# Sheet2.net
KiCad netlist of a schematic drawn in Altium Designer
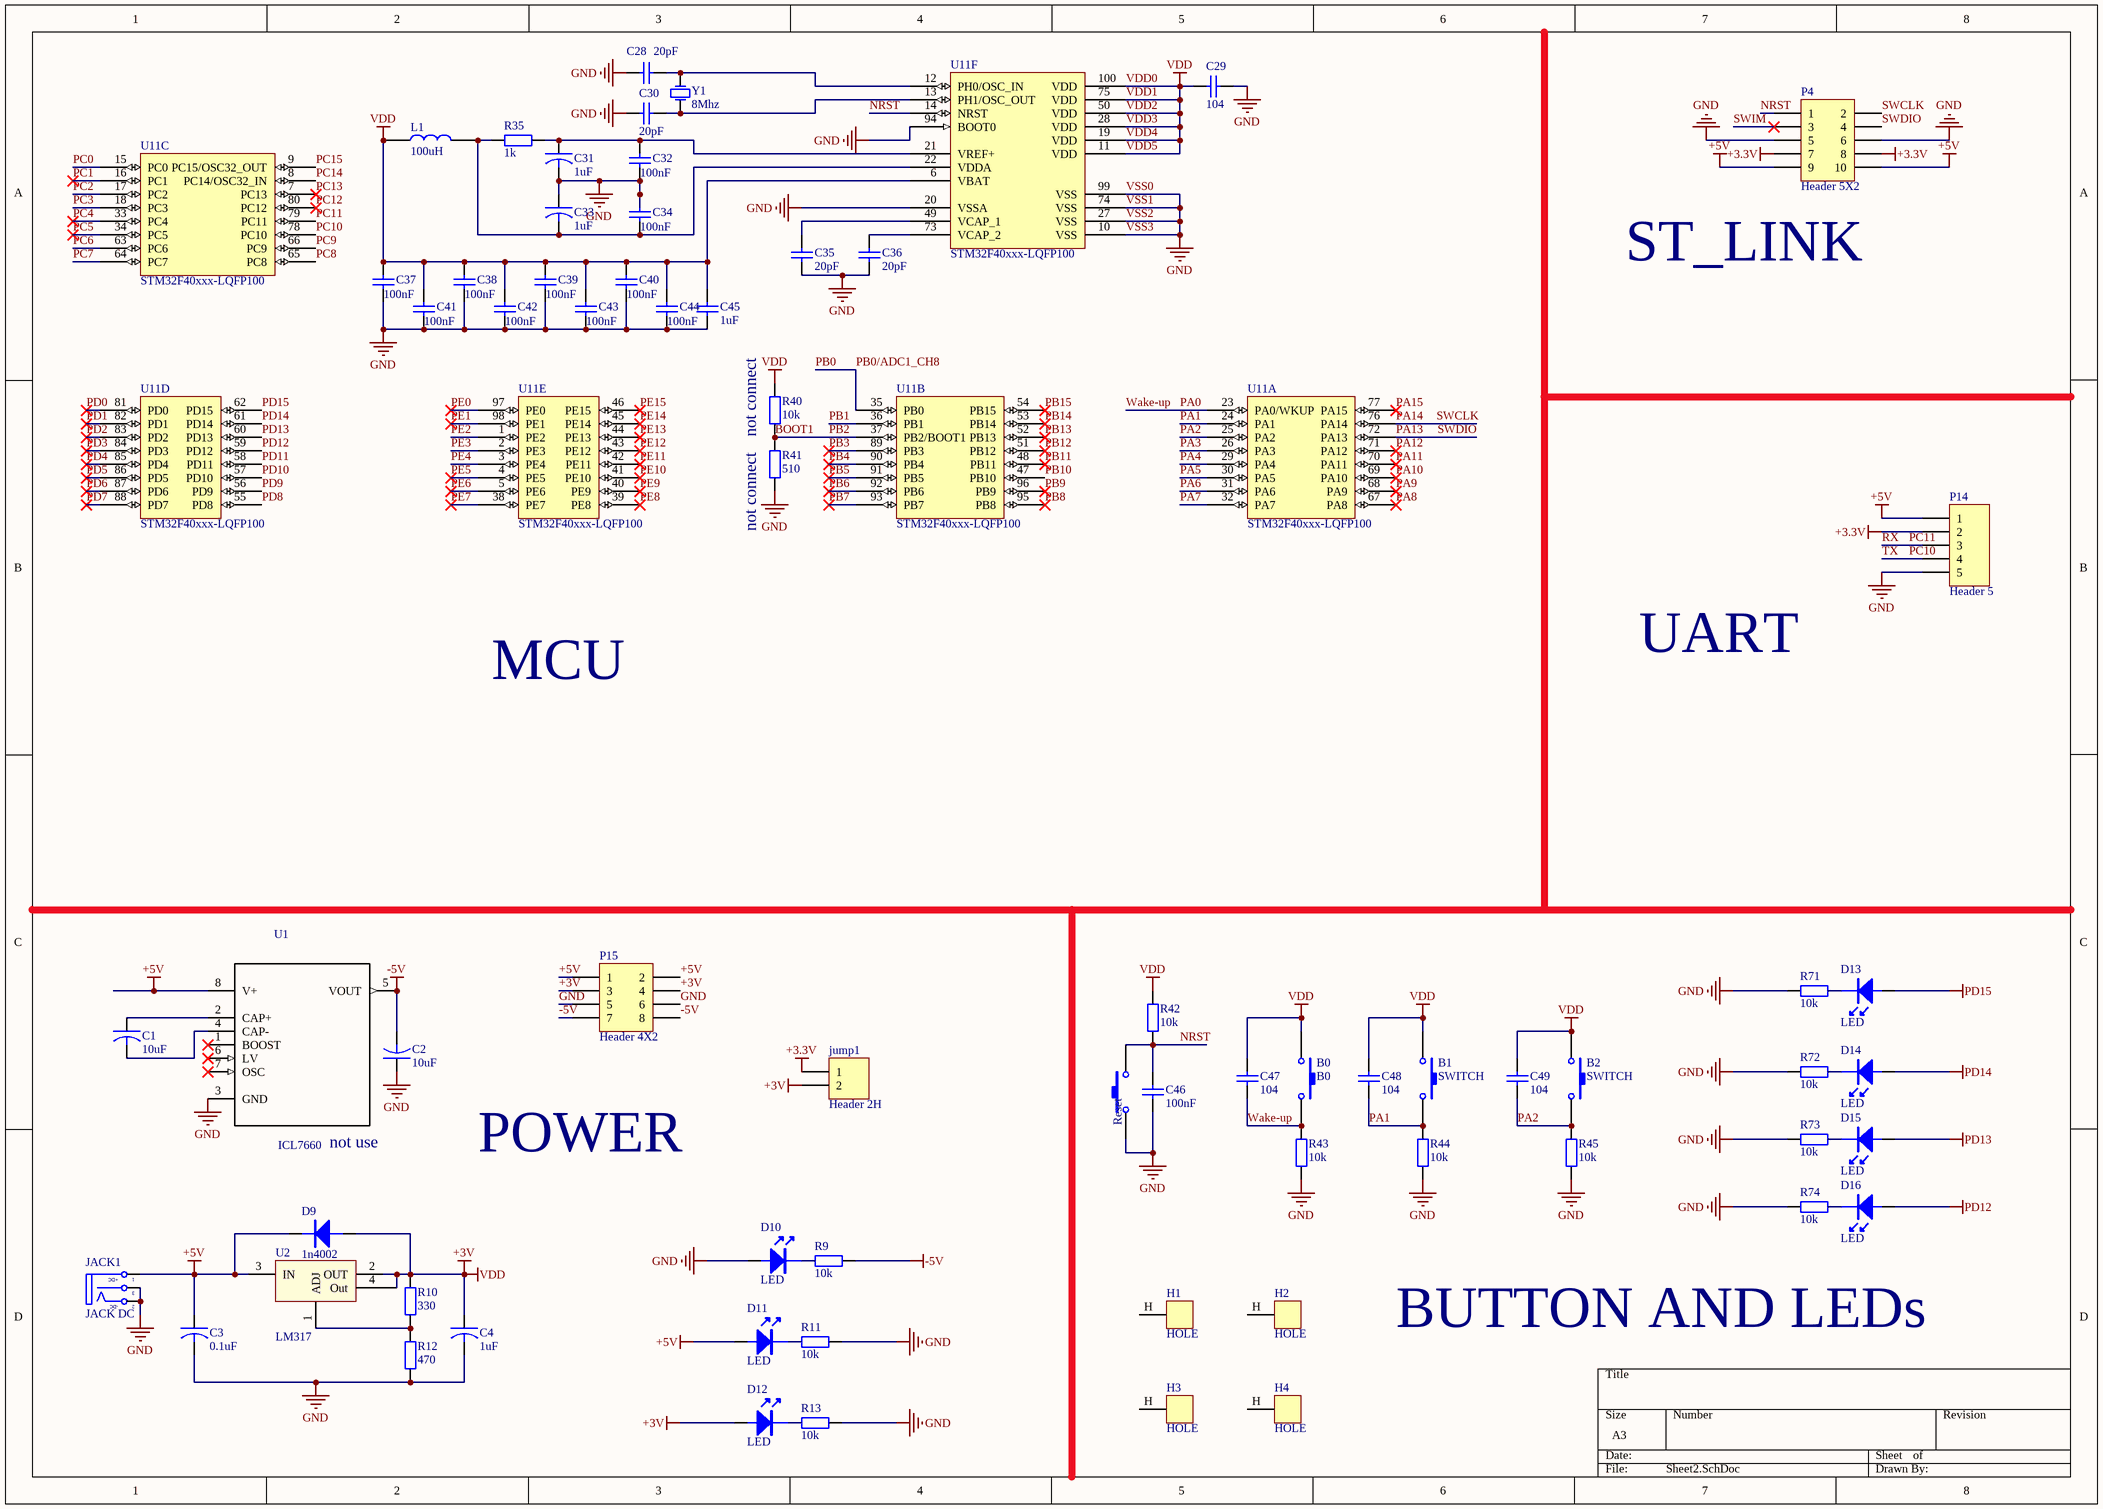
[diagram p0: Sheet2.SchDoc]

(export (version "E")
  (design (tool "Eeschema 10.0.6"))
  (components
    (comp (ref "B0")
      (value "B0")
      (footprint "SW 4PIN")
      (fields (field (name "PUBLISHER") "Altium Limited"))
      (libsource (lib "ThinhNguyenLib") (part "SWITCH"))
    )
    (comp (ref "B1")
      (value "SWITCH")
      (footprint "SW 4PIN")
      (fields (field (name "PUBLISHER") "Altium Limited"))
      (libsource (lib "ThinhNguyenLib") (part "SWITCH"))
    )
    (comp (ref "B2")
      (value "SWITCH")
      (footprint "SW 4PIN")
      (fields (field (name "PUBLISHER") "Altium Limited"))
      (libsource (lib "ThinhNguyenLib") (part "SWITCH"))
    )
    (comp (ref "C1")
      (value "10uF")
      (footprint "Miscellaneous Devices:3.5X2.8X1.9")
      (libsource (lib "ThinhNguyenLib") (part "CAPACITOR"))
    )
    (comp (ref "C2")
      (value "10uF")
      (footprint "Miscellaneous Devices:3.5X2.8X1.9")
      (libsource (lib "ThinhNguyenLib") (part "CAPACITOR"))
    )
    (comp (ref "C3")
      (value "0.1uF")
      (footprint "Miscellaneous Devices:3.5X2.8X1.9")
      (libsource (lib "ThinhNguyenLib") (part "CAPACITOR"))
    )
    (comp (ref "C4")
      (value "1uF")
      (footprint "Miscellaneous Devices:3.5X2.8X1.9")
      (libsource (lib "ThinhNguyenLib") (part "CAPACITOR"))
    )
    (comp (ref "C28")
      (value "20pF")
      (footprint "0805 CAP")
      (fields (field (name "PUBLISHER") "Altium Limited"))
      (libsource (lib "ThinhNguyenLib") (part "CAP CERAMIC"))
    )
    (comp (ref "C29")
      (value "104")
      (footprint "0805 CAP")
      (fields (field (name "PUBLISHER") "Altium Limited"))
      (libsource (lib "ThinhNguyenLib") (part "CAP CERAMIC"))
    )
    (comp (ref "C30")
      (value "20pF")
      (footprint "0805 CAP")
      (fields (field (name "PUBLISHER") "Altium Limited"))
      (libsource (lib "ThinhNguyenLib") (part "CAP CERAMIC"))
    )
    (comp (ref "C31")
      (value "1uF")
      (footprint "Miscellaneous Devices:3.5X2.8X1.9")
      (libsource (lib "ThinhNguyenLib") (part "CAPACITOR"))
    )
    (comp (ref "C32")
      (value "100nF")
      (footprint "0805 CAP")
      (fields (field (name "PUBLISHER") "Altium Limited"))
      (libsource (lib "ThinhNguyenLib") (part "CAP CERAMIC"))
    )
    (comp (ref "C33")
      (value "1uF")
      (footprint "Miscellaneous Devices:3.5X2.8X1.9")
      (libsource (lib "ThinhNguyenLib") (part "CAPACITOR"))
    )
    (comp (ref "C34")
      (value "100nF")
      (footprint "0805 CAP")
      (fields (field (name "PUBLISHER") "Altium Limited"))
      (libsource (lib "ThinhNguyenLib") (part "CAP CERAMIC"))
    )
    (comp (ref "C35")
      (value "20pF")
      (footprint "0805 CAP")
      (fields (field (name "PUBLISHER") "Altium Limited"))
      (libsource (lib "ThinhNguyenLib") (part "CAP CERAMIC"))
    )
    (comp (ref "C36")
      (value "20pF")
      (footprint "0805 CAP")
      (fields (field (name "PUBLISHER") "Altium Limited"))
      (libsource (lib "ThinhNguyenLib") (part "CAP CERAMIC"))
    )
    (comp (ref "C37")
      (value "100nF")
      (footprint "0805 CAP")
      (fields (field (name "PUBLISHER") "Altium Limited"))
      (libsource (lib "ThinhNguyenLib") (part "CAP CERAMIC"))
    )
    (comp (ref "C38")
      (value "100nF")
      (footprint "0805 CAP")
      (fields (field (name "PUBLISHER") "Altium Limited"))
      (libsource (lib "ThinhNguyenLib") (part "CAP CERAMIC"))
    )
    (comp (ref "C39")
      (value "100nF")
      (footprint "0805 CAP")
      (fields (field (name "PUBLISHER") "Altium Limited"))
      (libsource (lib "ThinhNguyenLib") (part "CAP CERAMIC"))
    )
    (comp (ref "C40")
      (value "100nF")
      (footprint "0805 CAP")
      (fields (field (name "PUBLISHER") "Altium Limited"))
      (libsource (lib "ThinhNguyenLib") (part "CAP CERAMIC"))
    )
    (comp (ref "C41")
      (value "100nF")
      (footprint "0805 CAP")
      (fields (field (name "PUBLISHER") "Altium Limited"))
      (libsource (lib "ThinhNguyenLib") (part "CAP CERAMIC"))
    )
    (comp (ref "C42")
      (value "100nF")
      (footprint "0805 CAP")
      (fields (field (name "PUBLISHER") "Altium Limited"))
      (libsource (lib "ThinhNguyenLib") (part "CAP CERAMIC"))
    )
    (comp (ref "C43")
      (value "100nF")
      (footprint "0805 CAP")
      (fields (field (name "PUBLISHER") "Altium Limited"))
      (libsource (lib "ThinhNguyenLib") (part "CAP CERAMIC"))
    )
    (comp (ref "C44")
      (value "100nF")
      (footprint "0805 CAP")
      (fields (field (name "PUBLISHER") "Altium Limited"))
      (libsource (lib "ThinhNguyenLib") (part "CAP CERAMIC"))
    )
    (comp (ref "C45")
      (value "1uF")
      (footprint "0805 CAP")
      (fields (field (name "PUBLISHER") "Altium Limited"))
      (libsource (lib "ThinhNguyenLib") (part "CAP CERAMIC"))
    )
    (comp (ref "C46")
      (value "100nF")
      (footprint "0805 CAP")
      (fields (field (name "PUBLISHER") "Altium Limited"))
      (libsource (lib "THINHDUILIB") (part "CAP CERAMIC"))
    )
    (comp (ref "C47")
      (value "104")
      (footprint "0805 CAP")
      (fields (field (name "PUBLISHER") "Altium Limited"))
      (libsource (lib "ThinhNguyenLib") (part "CAP CERAMIC"))
    )
    (comp (ref "C48")
      (value "104")
      (footprint "0805 CAP")
      (fields (field (name "PUBLISHER") "Altium Limited"))
      (libsource (lib "ThinhNguyenLib") (part "CAP CERAMIC"))
    )
    (comp (ref "C49")
      (value "104")
      (footprint "0805 CAP")
      (fields (field (name "PUBLISHER") "Altium Limited"))
      (libsource (lib "ThinhNguyenLib") (part "CAP CERAMIC"))
    )
    (comp (ref "D9")
      (value "1n4002")
      (footprint "DIODE SMA")
      (libsource (lib "ThinhNguyenLib") (part "DIODE"))
    )
    (comp (ref "D10")
      (value "LED")
      (footprint "LED SMD 0805")
      (libsource (lib "ThinhNguyenLib") (part "LED"))
    )
    (comp (ref "D11")
      (value "LED")
      (footprint "LED SMD 0805")
      (libsource (lib "ThinhNguyenLib") (part "LED"))
    )
    (comp (ref "D12")
      (value "LED")
      (footprint "LED SMD 0805")
      (libsource (lib "ThinhNguyenLib") (part "LED"))
    )
    (comp (ref "D13")
      (value "LED")
      (footprint "LED SMD 0805")
      (libsource (lib "ThinhNguyenLib") (part "LED"))
    )
    (comp (ref "D14")
      (value "LED")
      (footprint "LED SMD 0805")
      (libsource (lib "ThinhNguyenLib") (part "LED"))
    )
    (comp (ref "D15")
      (value "LED")
      (footprint "LED SMD 0805")
      (libsource (lib "ThinhNguyenLib") (part "LED"))
    )
    (comp (ref "D16")
      (value "LED")
      (footprint "LED SMD 0805")
      (libsource (lib "ThinhNguyenLib") (part "LED"))
    )
    (comp (ref "H1") (value "HOLE") (footprint "HOLE") (libsource (lib "ThinhNguyenLib") (part "HOLE")))
    (comp (ref "H2") (value "HOLE") (footprint "HOLE") (libsource (lib "ThinhNguyenLib") (part "HOLE")))
    (comp (ref "H3") (value "HOLE") (footprint "HOLE") (libsource (lib "ThinhNguyenLib") (part "HOLE")))
    (comp (ref "H4") (value "HOLE") (footprint "HOLE") (libsource (lib "ThinhNguyenLib") (part "HOLE")))
    (comp (ref "JACK1")
      (value "JACK DC")
      (footprint "JACK DC")
      (libsource (lib "ThinhNguyenLib") (part "JACK DC"))
    )
    (comp (ref "jump1")
      (value "Header 2H")
      (footprint "HDR1X2")
      (fields (field (name "PUBLISHER") "Altium Limited"))
      (libsource (lib "ThinhNguyenLib") (part "Header 2H"))
    )
    (comp (ref "L1")
      (value "100uH")
      (footprint "1206 Negro")
      (libsource (lib "ThinhNguyenLib") (part "INDUCTOR"))
    )
    (comp (ref "P4")
      (value "Header 5X2")
      (footprint "HDR2X5 2mm")
      (fields (field (name "PUBLISHER") "Altium Limited"))
      (libsource (lib "ThinhNguyenLib") (part "Header 5X2"))
    )
    (comp (ref "P14")
      (value "Header 5")
      (footprint "HDR1X5")
      (fields (field (name "PUBLISHER") "Altium Limited"))
      (libsource (lib "ThinhNguyenLib") (part "Header 5"))
    )
    (comp (ref "P15")
      (value "Header 4X2")
      (footprint "HDR2X4")
      (fields (field (name "PUBLISHER") "Altium Limited"))
      (libsource (lib "ThinhNguyenLib") (part "Header 4X2"))
    )
    (comp (ref "R9")
      (value "10k")
      (footprint "0805 RESISTOR")
      (libsource (lib "ThinhNguyenLib") (part "RESISTOR"))
    )
    (comp (ref "R10")
      (value "330")
      (footprint "0805 RESISTOR")
      (libsource (lib "THINHDUILIB") (part "RESISTOR"))
    )
    (comp (ref "R11")
      (value "10k")
      (footprint "0805 RESISTOR")
      (libsource (lib "ThinhNguyenLib") (part "RESISTOR"))
    )
    (comp (ref "R12")
      (value "470")
      (footprint "0805 RESISTOR")
      (libsource (lib "THINHDUILIB") (part "RESISTOR"))
    )
    (comp (ref "R13")
      (value "10k")
      (footprint "0805 RESISTOR")
      (libsource (lib "ThinhNguyenLib") (part "RESISTOR"))
    )
    (comp (ref "R35")
      (value "1k")
      (footprint "0805 RESISTOR")
      (libsource (lib "ThinhNguyenLib") (part "RESISTOR"))
    )
    (comp (ref "R40")
      (value "10k")
      (footprint "0805 RESISTOR")
      (libsource (lib "ThinhNguyenLib") (part "RESISTOR"))
    )
    (comp (ref "R41")
      (value "510")
      (footprint "0805 RESISTOR")
      (libsource (lib "ThinhNguyenLib") (part "RESISTOR"))
    )
    (comp (ref "R42")
      (value "10k")
      (footprint "0805 RESISTOR")
      (libsource (lib "THINHDUILIB") (part "RESISTOR"))
    )
    (comp (ref "R43")
      (value "10k")
      (footprint "0805 RESISTOR")
      (libsource (lib "ThinhNguyenLib") (part "RESISTOR"))
    )
    (comp (ref "R44")
      (value "10k")
      (footprint "0805 RESISTOR")
      (libsource (lib "ThinhNguyenLib") (part "RESISTOR"))
    )
    (comp (ref "R45")
      (value "10k")
      (footprint "0805 RESISTOR")
      (libsource (lib "ThinhNguyenLib") (part "RESISTOR"))
    )
    (comp (ref "R71")
      (value "10k")
      (footprint "0805 RESISTOR")
      (libsource (lib "ThinhNguyenLib") (part "RESISTOR"))
    )
    (comp (ref "R72")
      (value "10k")
      (footprint "0805 RESISTOR")
      (libsource (lib "ThinhNguyenLib") (part "RESISTOR"))
    )
    (comp (ref "R73")
      (value "10k")
      (footprint "0805 RESISTOR")
      (libsource (lib "ThinhNguyenLib") (part "RESISTOR"))
    )
    (comp (ref "R74")
      (value "10k")
      (footprint "0805 RESISTOR")
      (libsource (lib "ThinhNguyenLib") (part "RESISTOR"))
    )
    (comp (ref "Reset")
      (value "~")
      (footprint "SW 4PIN")
      (fields (field (name "PUBLISHER") "Altium Limited"))
      (libsource (lib "THINHDUILIB") (part "SWITCH"))
    )
    (comp (ref "U1")
      (value "ICL7660")
      (footprint "SOIC 8PIN")
      (description "ICL7660 Series 1.5 - 12 Vin 45 mA 10-35 kHz CMOS Voltage Converter - SOIC-8")
      (fields (field (name "MF") "Renesas Electronics") (field (name "MP") "ICL7660SIBAZ"))
      (libsource (lib "ICL7660SIBAZ") (part "ICL7660SIBAZ"))
    )
    (comp (ref "U2")
      (value "LM317")
      (footprint "SOT223-4N")
      (libsource (lib "ThinhNguyenLib") (part "LM317"))
    )
    (comp (ref "U11")
      (value "STM32F40xxx-LQFP100")
      (footprint "LQFP 100PIN")
      (libsource (lib "ThinhNguyenLib") (part "STM32F40xxx-LQFP100"))
    )
    (comp (ref "Y1")
      (value "8Mhz")
      (footprint "CRYSTAL DIP")
      (fields (field (name "PUBLISHER") "Altium Limited"))
      (libsource (lib "ThinhNguyenLib") (part "Crystal"))
    )
  )
  (nets
    (net (code "1") (name "+3.3V") (class "Default")
      (node (ref "P14") (pin "2") (pinfunction "2_2") (pintype "passive"))
      (node (ref "P4") (pin "7") (pinfunction "7_7") (pintype "passive"))
      (node (ref "P4") (pin "8") (pinfunction "8_8") (pintype "passive"))
      (node (ref "jump1") (pin "1") (pinfunction "1_1") (pintype "passive"))
    )
    (net (code "2") (name "+3V") (class "Default")
      (node (ref "B0") (pin "1") (pinfunction "1_1") (pintype "passive"))
      (node (ref "B1") (pin "1") (pinfunction "1_1") (pintype "passive"))
      (node (ref "B2") (pin "1") (pinfunction "1_1") (pintype "passive"))
      (node (ref "C29") (pin "1") (pinfunction "1_1") (pintype "passive"))
      (node (ref "C37") (pin "2") (pinfunction "2_2") (pintype "passive"))
      (node (ref "C38") (pin "2") (pinfunction "2_2") (pintype "passive"))
      (node (ref "C39") (pin "2") (pinfunction "2_2") (pintype "passive"))
      (node (ref "C4") (pin "1") (pinfunction "1_1") (pintype "passive"))
      (node (ref "C40") (pin "2") (pinfunction "2_2") (pintype "passive"))
      (node (ref "C41") (pin "2") (pinfunction "2_2") (pintype "passive"))
      (node (ref "C42") (pin "2") (pinfunction "2_2") (pintype "passive"))
      (node (ref "C43") (pin "2") (pinfunction "2_2") (pintype "passive"))
      (node (ref "C44") (pin "2") (pinfunction "2_2") (pintype "passive"))
      (node (ref "C45") (pin "2") (pinfunction "2_2") (pintype "passive"))
      (node (ref "C47") (pin "2") (pinfunction "2_2") (pintype "passive"))
      (node (ref "C48") (pin "2") (pinfunction "2_2") (pintype "passive"))
      (node (ref "C49") (pin "2") (pinfunction "2_2") (pintype "passive"))
      (node (ref "D12") (pin "1") (pinfunction "1_1") (pintype "passive"))
      (node (ref "D9") (pin "1") (pinfunction "1_1") (pintype "passive"))
      (node (ref "L1") (pin "1") (pinfunction "1_1") (pintype "passive"))
      (node (ref "P15") (pin "3") (pinfunction "3_3") (pintype "passive"))
      (node (ref "P15") (pin "4") (pinfunction "4_4") (pintype "passive"))
      (node (ref "R10") (pin "1") (pinfunction "1_1") (pintype "passive"))
      (node (ref "R40") (pin "2") (pinfunction "2_2") (pintype "passive"))
      (node (ref "R42") (pin "1") (pinfunction "1_1") (pintype "passive"))
      (node (ref "U11") (pin "100") (pinfunction "VDD_100") (pintype "power_in"))
      (node (ref "U11") (pin "11") (pinfunction "VDD_11") (pintype "power_in"))
      (node (ref "U11") (pin "19") (pinfunction "VDD_19") (pintype "power_in"))
      (node (ref "U11") (pin "28") (pinfunction "VDD_28") (pintype "power_in"))
      (node (ref "U11") (pin "50") (pinfunction "VDD_50") (pintype "power_in"))
      (node (ref "U11") (pin "6") (pinfunction "VBAT_6") (pintype "power_in"))
      (node (ref "U11") (pin "75") (pinfunction "VDD_75") (pintype "power_in"))
      (node (ref "U2") (pin "2") (pinfunction "OUT_2") (pintype "passive"))
      (node (ref "U2") (pin "4") (pinfunction "Out_4") (pintype "passive"))
      (node (ref "jump1") (pin "2") (pinfunction "2_2") (pintype "passive"))
    )
    (net (code "3") (name "+5V") (class "Default")
      (node (ref "C3") (pin "1") (pinfunction "1_1") (pintype "passive"))
      (node (ref "D11") (pin "1") (pinfunction "1_1") (pintype "passive"))
      (node (ref "D9") (pin "2") (pinfunction "2_2") (pintype "passive"))
      (node (ref "JACK1") (pin "1") (pinfunction "T_1") (pintype "passive"))
      (node (ref "P14") (pin "1") (pinfunction "1_1") (pintype "passive"))
      (node (ref "P15") (pin "1") (pinfunction "1_1") (pintype "passive"))
      (node (ref "P15") (pin "2") (pinfunction "2_2") (pintype "passive"))
      (node (ref "P4") (pin "10") (pinfunction "10_10") (pintype "passive"))
      (node (ref "P4") (pin "9") (pinfunction "9_9") (pintype "passive"))
      (node (ref "U1") (pin "8") (pinfunction "V+_8") (pintype "power_in"))
      (node (ref "U2") (pin "3") (pinfunction "IN_3") (pintype "passive"))
    )
    (net (code "4") (name "-5V") (class "Default")
      (node (ref "C2") (pin "2") (pinfunction "2_2") (pintype "passive"))
      (node (ref "P15") (pin "7") (pinfunction "7_7") (pintype "passive"))
      (node (ref "P15") (pin "8") (pinfunction "8_8") (pintype "passive"))
      (node (ref "R9") (pin "2") (pinfunction "2_2") (pintype "passive"))
      (node (ref "U1") (pin "5") (pinfunction "VOUT_5") (pintype "output"))
    )
    (net (code "5") (name "/BOOT1") (class "Default")
      (node (ref "R40") (pin "1") (pinfunction "1_1") (pintype "passive"))
      (node (ref "R41") (pin "2") (pinfunction "2_2") (pintype "passive"))
      (node (ref "U11") (pin "37") (pinfunction "PB2/BOOT1_37") (pintype "bidirectional"))
    )
    (net (code "6") (name "/NRST") (class "Default")
      (node (ref "C46") (pin "1") (pinfunction "1_1") (pintype "passive"))
      (node (ref "P4") (pin "1") (pinfunction "1_1") (pintype "passive"))
      (node (ref "R42") (pin "2") (pinfunction "2_2") (pintype "passive"))
      (node (ref "Reset") (pin "2") (pinfunction "2_2") (pintype "passive"))
      (node (ref "U11") (pin "14") (pinfunction "NRST_14") (pintype "bidirectional"))
    )
    (net (code "7") (name "/PA0") (class "Default")
      (node (ref "B0") (pin "2") (pinfunction "2_2") (pintype "passive"))
      (node (ref "C47") (pin "1") (pinfunction "1_1") (pintype "passive"))
      (node (ref "R43") (pin "2") (pinfunction "2_2") (pintype "passive"))
      (node (ref "U11") (pin "23") (pinfunction "PA0/WKUP_23") (pintype "bidirectional"))
    )
    (net (code "8") (name "/PA1") (class "Default")
      (node (ref "B1") (pin "2") (pinfunction "2_2") (pintype "passive"))
      (node (ref "C48") (pin "1") (pinfunction "1_1") (pintype "passive"))
      (node (ref "R44") (pin "2") (pinfunction "2_2") (pintype "passive"))
      (node (ref "U11") (pin "24") (pinfunction "PA1_24") (pintype "bidirectional"))
    )
    (net (code "9") (name "/PA2") (class "Default")
      (node (ref "B2") (pin "2") (pinfunction "2_2") (pintype "passive"))
      (node (ref "C49") (pin "1") (pinfunction "1_1") (pintype "passive"))
      (node (ref "R45") (pin "2") (pinfunction "2_2") (pintype "passive"))
      (node (ref "U11") (pin "25") (pinfunction "PA2_25") (pintype "bidirectional"))
    )
    (net (code "10") (name "/PA3") (class "Default")
      (node (ref "U11") (pin "26") (pinfunction "PA3_26") (pintype "bidirectional"))
    )
    (net (code "11") (name "/PA4") (class "Default")
      (node (ref "U11") (pin "29") (pinfunction "PA4_29") (pintype "bidirectional"))
    )
    (net (code "12") (name "/PA5") (class "Default")
      (node (ref "U11") (pin "30") (pinfunction "PA5_30") (pintype "bidirectional"))
    )
    (net (code "13") (name "/PA6") (class "Default")
      (node (ref "U11") (pin "31") (pinfunction "PA6_31") (pintype "bidirectional"))
    )
    (net (code "14") (name "/PA7") (class "Default")
      (node (ref "U11") (pin "32") (pinfunction "PA7_32") (pintype "bidirectional"))
    )
    (net (code "15") (name "/PA8") (class "Default")
      (node (ref "U11") (pin "67") (pinfunction "PA8_67") (pintype "bidirectional+no_connect"))
    )
    (net (code "16") (name "/PA9") (class "Default")
      (node (ref "U11") (pin "68") (pinfunction "PA9_68") (pintype "bidirectional+no_connect"))
    )
    (net (code "17") (name "/PA10") (class "Default")
      (node (ref "U11") (pin "69") (pinfunction "PA10_69") (pintype "bidirectional+no_connect"))
    )
    (net (code "18") (name "/PA11") (class "Default")
      (node (ref "U11") (pin "70") (pinfunction "PA11_70") (pintype "bidirectional+no_connect"))
    )
    (net (code "19") (name "/PA12") (class "Default")
      (node (ref "U11") (pin "71") (pinfunction "PA12_71") (pintype "bidirectional+no_connect"))
    )
    (net (code "20") (name "/PA13") (class "Default")
      (node (ref "P4") (pin "4") (pinfunction "4_4") (pintype "passive"))
      (node (ref "U11") (pin "72") (pinfunction "PA13_72") (pintype "bidirectional"))
    )
    (net (code "21") (name "/PA14") (class "Default")
      (node (ref "P4") (pin "2") (pinfunction "2_2") (pintype "passive"))
      (node (ref "U11") (pin "76") (pinfunction "PA14_76") (pintype "bidirectional"))
    )
    (net (code "22") (name "/PA15") (class "Default")
      (node (ref "U11") (pin "77") (pinfunction "PA15_77") (pintype "bidirectional+no_connect"))
    )
    (net (code "23") (name "/PB0") (class "Default")
      (node (ref "U11") (pin "35") (pinfunction "PB0_35") (pintype "bidirectional"))
    )
    (net (code "24") (name "/PB1") (class "Default")
      (node (ref "U11") (pin "36") (pinfunction "PB1_36") (pintype "bidirectional"))
    )
    (net (code "25") (name "/PB3") (class "Default")
      (node (ref "U11") (pin "89") (pinfunction "PB3_89") (pintype "bidirectional+no_connect"))
    )
    (net (code "26") (name "/PB4") (class "Default")
      (node (ref "U11") (pin "90") (pinfunction "PB4_90") (pintype "bidirectional+no_connect"))
    )
    (net (code "27") (name "/PB5") (class "Default")
      (node (ref "U11") (pin "91") (pinfunction "PB5_91") (pintype "bidirectional+no_connect"))
    )
    (net (code "28") (name "/PB6") (class "Default")
      (node (ref "U11") (pin "92") (pinfunction "PB6_92") (pintype "bidirectional+no_connect"))
    )
    (net (code "29") (name "/PB7") (class "Default")
      (node (ref "U11") (pin "93") (pinfunction "PB7_93") (pintype "bidirectional+no_connect"))
    )
    (net (code "30") (name "/PB8") (class "Default")
      (node (ref "U11") (pin "95") (pinfunction "PB8_95") (pintype "bidirectional+no_connect"))
    )
    (net (code "31") (name "/PB9") (class "Default")
      (node (ref "U11") (pin "96") (pinfunction "PB9_96") (pintype "bidirectional+no_connect"))
    )
    (net (code "32") (name "/PB10") (class "Default")
      (node (ref "U11") (pin "47") (pinfunction "PB10_47") (pintype "bidirectional"))
    )
    (net (code "33") (name "/PB11") (class "Default")
      (node (ref "U11") (pin "48") (pinfunction "PB11_48") (pintype "bidirectional+no_connect"))
    )
    (net (code "34") (name "/PB12") (class "Default")
      (node (ref "U11") (pin "51") (pinfunction "PB12_51") (pintype "bidirectional+no_connect"))
    )
    (net (code "35") (name "/PB13") (class "Default")
      (node (ref "U11") (pin "52") (pinfunction "PB13_52") (pintype "bidirectional+no_connect"))
    )
    (net (code "36") (name "/PB14") (class "Default")
      (node (ref "U11") (pin "53") (pinfunction "PB14_53") (pintype "bidirectional+no_connect"))
    )
    (net (code "37") (name "/PB15") (class "Default")
      (node (ref "U11") (pin "54") (pinfunction "PB15_54") (pintype "bidirectional+no_connect"))
    )
    (net (code "38") (name "/PC0") (class "Default")
      (node (ref "U11") (pin "15") (pinfunction "PC0_15") (pintype "bidirectional"))
    )
    (net (code "39") (name "/PC1") (class "Default")
      (node (ref "U11") (pin "16") (pinfunction "PC1_16") (pintype "bidirectional+no_connect"))
    )
    (net (code "40") (name "/PC2") (class "Default")
      (node (ref "U11") (pin "17") (pinfunction "PC2_17") (pintype "bidirectional"))
    )
    (net (code "41") (name "/PC3") (class "Default")
      (node (ref "U11") (pin "18") (pinfunction "PC3_18") (pintype "bidirectional"))
    )
    (net (code "42") (name "/PC4") (class "Default")
      (node (ref "U11") (pin "33") (pinfunction "PC4_33") (pintype "bidirectional+no_connect"))
    )
    (net (code "43") (name "/PC5") (class "Default")
      (node (ref "U11") (pin "34") (pinfunction "PC5_34") (pintype "bidirectional+no_connect"))
    )
    (net (code "44") (name "/PC6") (class "Default")
      (node (ref "U11") (pin "63") (pinfunction "PC6_63") (pintype "bidirectional"))
    )
    (net (code "45") (name "/PC7") (class "Default")
      (node (ref "U11") (pin "64") (pinfunction "PC7_64") (pintype "bidirectional"))
    )
    (net (code "46") (name "/PC8") (class "Default")
      (node (ref "U11") (pin "65") (pinfunction "PC8_65") (pintype "bidirectional"))
    )
    (net (code "47") (name "/PC9") (class "Default")
      (node (ref "U11") (pin "66") (pinfunction "PC9_66") (pintype "bidirectional"))
    )
    (net (code "48") (name "/PC10") (class "Default")
      (node (ref "P14") (pin "4") (pinfunction "4_4") (pintype "passive"))
      (node (ref "U11") (pin "78") (pinfunction "PC10_78") (pintype "bidirectional"))
    )
    (net (code "49") (name "/PC11") (class "Default")
      (node (ref "P14") (pin "3") (pinfunction "3_3") (pintype "passive"))
      (node (ref "U11") (pin "79") (pinfunction "PC11_79") (pintype "bidirectional"))
    )
    (net (code "50") (name "/PC12") (class "Default")
      (node (ref "U11") (pin "80") (pinfunction "PC12_80") (pintype "bidirectional+no_connect"))
    )
    (net (code "51") (name "/PC13") (class "Default")
      (node (ref "U11") (pin "7") (pinfunction "PC13_7") (pintype "bidirectional+no_connect"))
    )
    (net (code "52") (name "/PC14") (class "Default")
      (node (ref "U11") (pin "8") (pinfunction "PC14/OSC32_IN_8") (pintype "bidirectional"))
    )
    (net (code "53") (name "/PC15") (class "Default")
      (node (ref "U11") (pin "9") (pinfunction "PC15/OSC32_OUT_9") (pintype "bidirectional"))
    )
    (net (code "54") (name "/PD0") (class "Default")
      (node (ref "U11") (pin "81") (pinfunction "PD0_81") (pintype "bidirectional+no_connect"))
    )
    (net (code "55") (name "/PD1") (class "Default")
      (node (ref "U11") (pin "82") (pinfunction "PD1_82") (pintype "bidirectional+no_connect"))
    )
    (net (code "56") (name "/PD2") (class "Default")
      (node (ref "U11") (pin "83") (pinfunction "PD2_83") (pintype "bidirectional+no_connect"))
    )
    (net (code "57") (name "/PD3") (class "Default")
      (node (ref "U11") (pin "84") (pinfunction "PD3_84") (pintype "bidirectional+no_connect"))
    )
    (net (code "58") (name "/PD4") (class "Default")
      (node (ref "U11") (pin "85") (pinfunction "PD4_85") (pintype "bidirectional+no_connect"))
    )
    (net (code "59") (name "/PD5") (class "Default")
      (node (ref "U11") (pin "86") (pinfunction "PD5_86") (pintype "bidirectional+no_connect"))
    )
    (net (code "60") (name "/PD6") (class "Default")
      (node (ref "U11") (pin "87") (pinfunction "PD6_87") (pintype "bidirectional+no_connect"))
    )
    (net (code "61") (name "/PD7") (class "Default")
      (node (ref "U11") (pin "88") (pinfunction "PD7_88") (pintype "bidirectional+no_connect"))
    )
    (net (code "62") (name "/PD8") (class "Default")
      (node (ref "U11") (pin "55") (pinfunction "PD8_55") (pintype "bidirectional"))
    )
    (net (code "63") (name "/PD9") (class "Default")
      (node (ref "U11") (pin "56") (pinfunction "PD9_56") (pintype "bidirectional"))
    )
    (net (code "64") (name "/PD10") (class "Default")
      (node (ref "U11") (pin "57") (pinfunction "PD10_57") (pintype "bidirectional"))
    )
    (net (code "65") (name "/PD11") (class "Default")
      (node (ref "U11") (pin "58") (pinfunction "PD11_58") (pintype "bidirectional"))
    )
    (net (code "66") (name "/PE0") (class "Default")
      (node (ref "U11") (pin "97") (pinfunction "PE0_97") (pintype "bidirectional+no_connect"))
    )
    (net (code "67") (name "/PE1") (class "Default")
      (node (ref "U11") (pin "98") (pinfunction "PE1_98") (pintype "bidirectional+no_connect"))
    )
    (net (code "68") (name "/PE2") (class "Default")
      (node (ref "U11") (pin "1") (pinfunction "PE2_1") (pintype "bidirectional"))
    )
    (net (code "69") (name "/PE3") (class "Default")
      (node (ref "U11") (pin "2") (pinfunction "PE3_2") (pintype "bidirectional"))
    )
    (net (code "70") (name "/PE4") (class "Default")
      (node (ref "U11") (pin "3") (pinfunction "PE4_3") (pintype "bidirectional"))
    )
    (net (code "71") (name "/PE5") (class "Default")
      (node (ref "U11") (pin "4") (pinfunction "PE5_4") (pintype "bidirectional+no_connect"))
    )
    (net (code "72") (name "/PE6") (class "Default")
      (node (ref "U11") (pin "5") (pinfunction "PE6_5") (pintype "bidirectional+no_connect"))
    )
    (net (code "73") (name "/PE7") (class "Default")
      (node (ref "U11") (pin "38") (pinfunction "PE7_38") (pintype "bidirectional+no_connect"))
    )
    (net (code "74") (name "/PE8") (class "Default")
      (node (ref "U11") (pin "39") (pinfunction "PE8_39") (pintype "bidirectional+no_connect"))
    )
    (net (code "75") (name "/PE9") (class "Default")
      (node (ref "U11") (pin "40") (pinfunction "PE9_40") (pintype "bidirectional+no_connect"))
    )
    (net (code "76") (name "/PE10") (class "Default")
      (node (ref "U11") (pin "41") (pinfunction "PE10_41") (pintype "bidirectional+no_connect"))
    )
    (net (code "77") (name "/PE11") (class "Default")
      (node (ref "U11") (pin "42") (pinfunction "PE11_42") (pintype "bidirectional+no_connect"))
    )
    (net (code "78") (name "/PE12") (class "Default")
      (node (ref "U11") (pin "43") (pinfunction "PE12_43") (pintype "bidirectional+no_connect"))
    )
    (net (code "79") (name "/PE13") (class "Default")
      (node (ref "U11") (pin "44") (pinfunction "PE13_44") (pintype "bidirectional+no_connect"))
    )
    (net (code "80") (name "/PE14") (class "Default")
      (node (ref "U11") (pin "45") (pinfunction "PE14_45") (pintype "bidirectional+no_connect"))
    )
    (net (code "81") (name "/PE15") (class "Default")
      (node (ref "U11") (pin "46") (pinfunction "PE15_46") (pintype "bidirectional+no_connect"))
    )
    (net (code "82") (name "/SWIM") (class "Default")
      (node (ref "P4") (pin "3") (pinfunction "3_3") (pintype "passive+no_connect"))
    )
    (net (code "83") (name "GND") (class "Default")
      (node (ref "C2") (pin "1") (pinfunction "1_1") (pintype "passive"))
      (node (ref "C28") (pin "1") (pinfunction "1_1") (pintype "passive"))
      (node (ref "C29") (pin "2") (pinfunction "2_2") (pintype "passive"))
      (node (ref "C3") (pin "2") (pinfunction "2_2") (pintype "passive"))
      (node (ref "C30") (pin "1") (pinfunction "1_1") (pintype "passive"))
      (node (ref "C31") (pin "2") (pinfunction "2_2") (pintype "passive"))
      (node (ref "C32") (pin "1") (pinfunction "1_1") (pintype "passive"))
      (node (ref "C33") (pin "1") (pinfunction "1_1") (pintype "passive"))
      (node (ref "C34") (pin "2") (pinfunction "2_2") (pintype "passive"))
      (node (ref "C35") (pin "1") (pinfunction "1_1") (pintype "passive"))
      (node (ref "C36") (pin "1") (pinfunction "1_1") (pintype "passive"))
      (node (ref "C37") (pin "1") (pinfunction "1_1") (pintype "passive"))
      (node (ref "C38") (pin "1") (pinfunction "1_1") (pintype "passive"))
      (node (ref "C39") (pin "1") (pinfunction "1_1") (pintype "passive"))
      (node (ref "C4") (pin "2") (pinfunction "2_2") (pintype "passive"))
      (node (ref "C40") (pin "1") (pinfunction "1_1") (pintype "passive"))
      (node (ref "C41") (pin "1") (pinfunction "1_1") (pintype "passive"))
      (node (ref "C42") (pin "1") (pinfunction "1_1") (pintype "passive"))
      (node (ref "C43") (pin "1") (pinfunction "1_1") (pintype "passive"))
      (node (ref "C44") (pin "1") (pinfunction "1_1") (pintype "passive"))
      (node (ref "C45") (pin "1") (pinfunction "1_1") (pintype "passive"))
      (node (ref "C46") (pin "2") (pinfunction "2_2") (pintype "passive"))
      (node (ref "D10") (pin "1") (pinfunction "1_1") (pintype "passive"))
      (node (ref "JACK1") (pin "2") (pinfunction "TN_2") (pintype "passive"))
      (node (ref "JACK1") (pin "3") (pinfunction "S_3") (pintype "power_in"))
      (node (ref "P14") (pin "5") (pinfunction "5_5") (pintype "passive"))
      (node (ref "P15") (pin "5") (pinfunction "5_5") (pintype "passive"))
      (node (ref "P15") (pin "6") (pinfunction "6_6") (pintype "passive"))
      (node (ref "P4") (pin "5") (pinfunction "5_5") (pintype "passive"))
      (node (ref "P4") (pin "6") (pinfunction "6_6") (pintype "passive"))
      (node (ref "R11") (pin "2") (pinfunction "2_2") (pintype "passive"))
      (node (ref "R12") (pin "2") (pinfunction "2_2") (pintype "passive"))
      (node (ref "R13") (pin "2") (pinfunction "2_2") (pintype "passive"))
      (node (ref "R41") (pin "1") (pinfunction "1_1") (pintype "passive"))
      (node (ref "R43") (pin "1") (pinfunction "1_1") (pintype "passive"))
      (node (ref "R44") (pin "1") (pinfunction "1_1") (pintype "passive"))
      (node (ref "R45") (pin "1") (pinfunction "1_1") (pintype "passive"))
      (node (ref "R71") (pin "2") (pinfunction "2_2") (pintype "passive"))
      (node (ref "R72") (pin "2") (pinfunction "2_2") (pintype "passive"))
      (node (ref "R73") (pin "2") (pinfunction "2_2") (pintype "passive"))
      (node (ref "R74") (pin "2") (pinfunction "2_2") (pintype "passive"))
      (node (ref "Reset") (pin "1") (pinfunction "1_1") (pintype "passive"))
      (node (ref "U1") (pin "3") (pinfunction "GND_3") (pintype "passive"))
      (node (ref "U11") (pin "10") (pinfunction "VSS_10") (pintype "power_in"))
      (node (ref "U11") (pin "20") (pinfunction "VSSA_20") (pintype "power_in"))
      (node (ref "U11") (pin "27") (pinfunction "VSS_27") (pintype "power_in"))
      (node (ref "U11") (pin "74") (pinfunction "VSS_74") (pintype "power_in"))
      (node (ref "U11") (pin "94") (pinfunction "BOOT0_94") (pintype "input"))
      (node (ref "U11") (pin "99") (pinfunction "VSS_99") (pintype "power_in"))
    )
    (net (code "84") (name "Net-(D10-Pad2)") (class "Default")
      (node (ref "D10") (pin "2") (pinfunction "2_2") (pintype "passive"))
      (node (ref "R9") (pin "1") (pinfunction "1_1") (pintype "passive"))
    )
    (net (code "85") (name "Net-(D11-Pad2)") (class "Default")
      (node (ref "D11") (pin "2") (pinfunction "2_2") (pintype "passive"))
      (node (ref "R11") (pin "1") (pinfunction "1_1") (pintype "passive"))
    )
    (net (code "86") (name "Net-(D12-Pad2)") (class "Default")
      (node (ref "D12") (pin "2") (pinfunction "2_2") (pintype "passive"))
      (node (ref "R13") (pin "1") (pinfunction "1_1") (pintype "passive"))
    )
    (net (code "87") (name "Net-(D13-Pad2)") (class "Default")
      (node (ref "D13") (pin "2") (pinfunction "2_2") (pintype "passive"))
      (node (ref "R71") (pin "1") (pinfunction "1_1") (pintype "passive"))
    )
    (net (code "88") (name "Net-(D14-Pad2)") (class "Default")
      (node (ref "D14") (pin "2") (pinfunction "2_2") (pintype "passive"))
      (node (ref "R72") (pin "1") (pinfunction "1_1") (pintype "passive"))
    )
    (net (code "89") (name "Net-(D15-Pad2)") (class "Default")
      (node (ref "D15") (pin "2") (pinfunction "2_2") (pintype "passive"))
      (node (ref "R73") (pin "1") (pinfunction "1_1") (pintype "passive"))
    )
    (net (code "90") (name "Net-(D16-Pad2)") (class "Default")
      (node (ref "D16") (pin "2") (pinfunction "2_2") (pintype "passive"))
      (node (ref "R74") (pin "1") (pinfunction "1_1") (pintype "passive"))
    )
    (net (code "91") (name "Net-(U1-CAP+)") (class "Default")
      (node (ref "C1") (pin "1") (pinfunction "1_1") (pintype "passive"))
      (node (ref "U1") (pin "2") (pinfunction "CAP+_2") (pintype "passive"))
    )
    (net (code "92") (name "Net-(U1-CAP-)") (class "Default")
      (node (ref "C1") (pin "2") (pinfunction "2_2") (pintype "passive"))
      (node (ref "U1") (pin "4") (pinfunction "CAP-_4") (pintype "passive"))
    )
    (net (code "93") (name "Net-(U2-ADJ)") (class "Default")
      (node (ref "R10") (pin "2") (pinfunction "2_2") (pintype "passive"))
      (node (ref "R12") (pin "1") (pinfunction "1_1") (pintype "passive"))
      (node (ref "U2") (pin "1") (pinfunction "ADJ_1") (pintype "passive"))
    )
    (net (code "94") (name "Net-(U11F-PH0{slash}OSC_IN)") (class "Default")
      (node (ref "C28") (pin "2") (pinfunction "2_2") (pintype "passive"))
      (node (ref "U11") (pin "12") (pinfunction "PH0/OSC_IN_12") (pintype "bidirectional"))
      (node (ref "Y1") (pin "2") (pinfunction "OSC2_2") (pintype "passive"))
    )
    (net (code "95") (name "Net-(U11F-PH1{slash}OSC_OUT)") (class "Default")
      (node (ref "C30") (pin "2") (pinfunction "2_2") (pintype "passive"))
      (node (ref "U11") (pin "13") (pinfunction "PH1/OSC_OUT_13") (pintype "bidirectional"))
      (node (ref "Y1") (pin "1") (pinfunction "OSC1_1") (pintype "passive"))
    )
    (net (code "96") (name "Net-(U11F-VCAP_1)") (class "Default")
      (node (ref "C35") (pin "2") (pinfunction "2_2") (pintype "passive"))
      (node (ref "U11") (pin "49") (pinfunction "VCAP_1_49") (pintype "power_in"))
    )
    (net (code "97") (name "Net-(U11F-VCAP_2)") (class "Default")
      (node (ref "C36") (pin "2") (pinfunction "2_2") (pintype "passive"))
      (node (ref "U11") (pin "73") (pinfunction "VCAP_2_73") (pintype "power_in"))
    )
    (net (code "98") (name "Net-(U11F-VDDA)") (class "Default")
      (node (ref "C33") (pin "2") (pinfunction "2_2") (pintype "passive"))
      (node (ref "C34") (pin "1") (pinfunction "1_1") (pintype "passive"))
      (node (ref "L1") (pin "2") (pinfunction "2_2") (pintype "passive"))
      (node (ref "R35") (pin "1") (pinfunction "1_1") (pintype "passive"))
      (node (ref "U11") (pin "22") (pinfunction "VDDA_22") (pintype "power_in"))
    )
    (net (code "99") (name "Net-(U11F-VREF+)") (class "Default")
      (node (ref "C31") (pin "1") (pinfunction "1_1") (pintype "passive"))
      (node (ref "C32") (pin "2") (pinfunction "2_2") (pintype "passive"))
      (node (ref "R35") (pin "2") (pinfunction "2_2") (pintype "passive"))
      (node (ref "U11") (pin "21") (pinfunction "VREF+_21") (pintype "power_in"))
    )
    (net (code "100") (name "PD12") (class "Default")
      (node (ref "D16") (pin "1") (pinfunction "1_1") (pintype "passive"))
      (node (ref "U11") (pin "59") (pinfunction "PD12_59") (pintype "bidirectional"))
    )
    (net (code "101") (name "PD13") (class "Default")
      (node (ref "D15") (pin "1") (pinfunction "1_1") (pintype "passive"))
      (node (ref "U11") (pin "60") (pinfunction "PD13_60") (pintype "bidirectional"))
    )
    (net (code "102") (name "PD14") (class "Default")
      (node (ref "D14") (pin "1") (pinfunction "1_1") (pintype "passive"))
      (node (ref "U11") (pin "61") (pinfunction "PD14_61") (pintype "bidirectional"))
    )
    (net (code "103") (name "PD15") (class "Default")
      (node (ref "D13") (pin "1") (pinfunction "1_1") (pintype "passive"))
      (node (ref "U11") (pin "62") (pinfunction "PD15_62") (pintype "bidirectional"))
    )
    (net (code "104") (name "unconnected-(H1-HOLE-PadH)") (class "Default")
      (node (ref "H1") (pin "H") (pinfunction "HOLE_H") (pintype "passive"))
    )
    (net (code "105") (name "unconnected-(H2-HOLE-PadH)") (class "Default")
      (node (ref "H2") (pin "H") (pinfunction "HOLE_H") (pintype "passive"))
    )
    (net (code "106") (name "unconnected-(H3-HOLE-PadH)") (class "Default")
      (node (ref "H3") (pin "H") (pinfunction "HOLE_H") (pintype "passive"))
    )
    (net (code "107") (name "unconnected-(H4-HOLE-PadH)") (class "Default")
      (node (ref "H4") (pin "H") (pinfunction "HOLE_H") (pintype "passive"))
    )
    (net (code "108") (name "unconnected-(U1-BOOST-Pad1)") (class "Default")
      (node (ref "U1") (pin "1") (pinfunction "BOOST_1") (pintype "power_in+no_connect"))
    )
    (net (code "109") (name "unconnected-(U1-LV-Pad6)") (class "Default")
      (node (ref "U1") (pin "6") (pinfunction "LV_6") (pintype "input+no_connect"))
    )
    (net (code "110") (name "unconnected-(U1-OSC-Pad7)") (class "Default")
      (node (ref "U1") (pin "7") (pinfunction "OSC_7") (pintype "input+no_connect"))
    )
  )
)
